# OwlModular.net
KiCad netlist of a schematic drawn in EAGLE
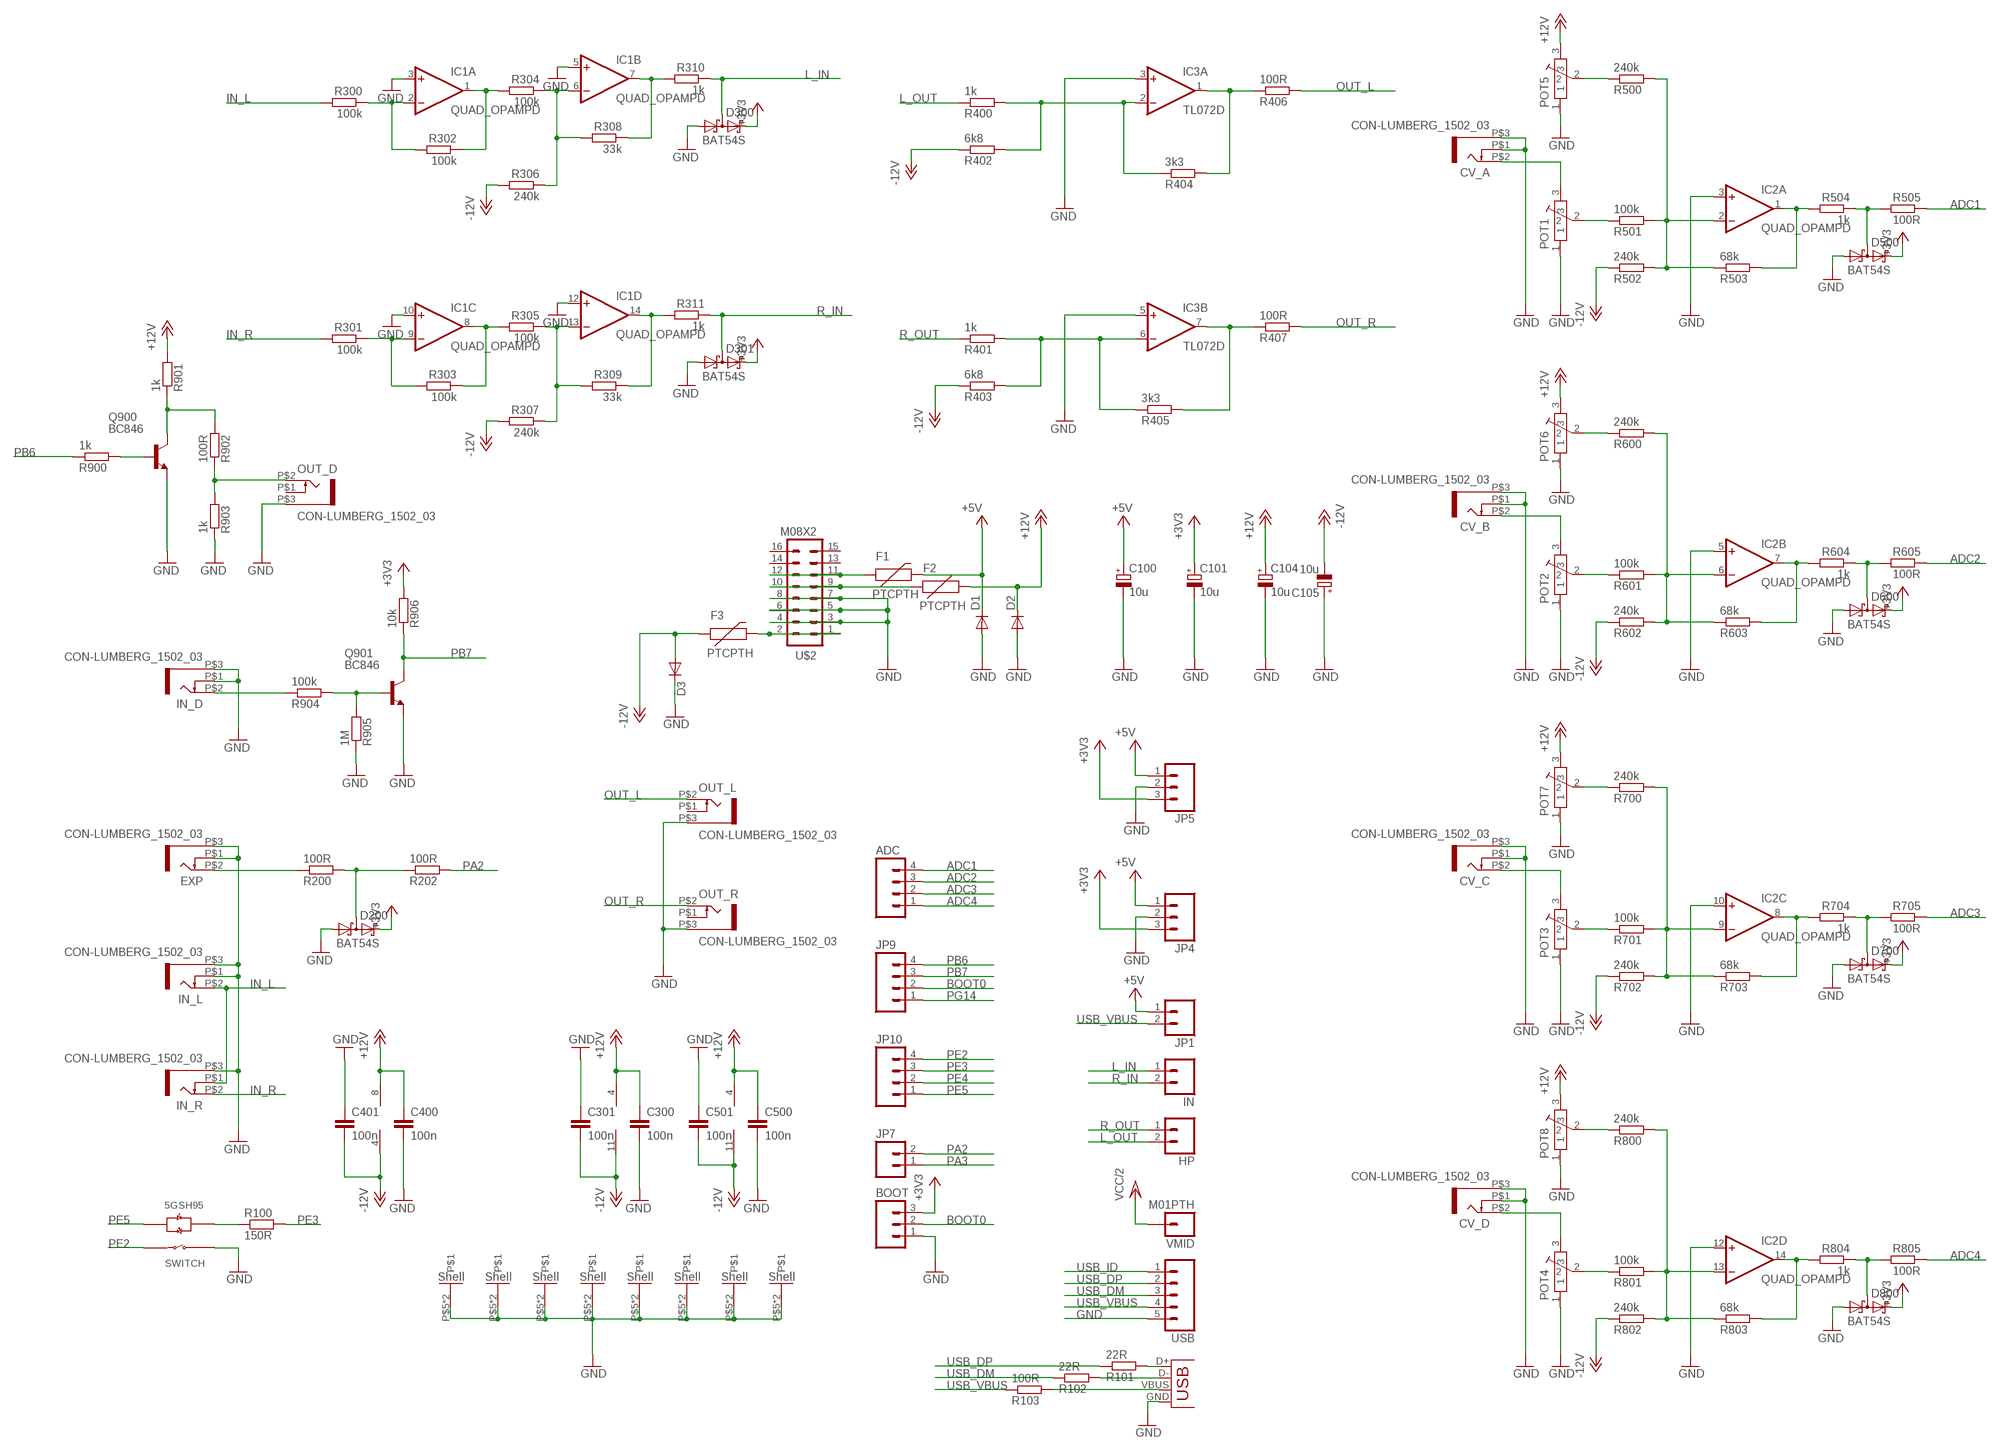
[diagram p0: schematic, sheet 1]

(export (version "E")
  (design (tool "Eeschema 10.0.6"))
  (components
    (comp (ref "ADC")
      (value "M04PTH")
      (footprint "eagle-import:1X04")
      (libsource (lib "eagle-import") (part "M04PTH"))
    )
    (comp (ref "BOOT")
      (value "M03PTH")
      (footprint "eagle-import:1X03")
      (libsource (lib "eagle-import") (part "M03PTH"))
    )
    (comp (ref "C100")
      (value "10u")
      (footprint "eagle-import:PANASONIC_A")
      (libsource (lib "eagle-import") (part "CPOL-EUA"))
    )
    (comp (ref "C101")
      (value "10u")
      (footprint "eagle-import:PANASONIC_A")
      (libsource (lib "eagle-import") (part "CPOL-EUA"))
    )
    (comp (ref "C104")
      (value "10u")
      (footprint "eagle-import:PANASONIC_A")
      (libsource (lib "eagle-import") (part "CPOL-EUA"))
    )
    (comp (ref "C105")
      (value "10u")
      (footprint "eagle-import:PANASONIC_A")
      (libsource (lib "eagle-import") (part "CPOL-EUA"))
    )
    (comp (ref "C300")
      (value "100n")
      (footprint "eagle-import:C0603")
      (libsource (lib "eagle-import") (part "C-EUC0603"))
    )
    (comp (ref "C301")
      (value "100n")
      (footprint "eagle-import:C0603")
      (libsource (lib "eagle-import") (part "C-EUC0603"))
    )
    (comp (ref "C400")
      (value "100n")
      (footprint "eagle-import:C0603")
      (libsource (lib "eagle-import") (part "C-EUC0603"))
    )
    (comp (ref "C401")
      (value "100n")
      (footprint "eagle-import:C0603")
      (libsource (lib "eagle-import") (part "C-EUC0603"))
    )
    (comp (ref "C500")
      (value "100n")
      (footprint "eagle-import:C0603")
      (libsource (lib "eagle-import") (part "C-EUC0603"))
    )
    (comp (ref "C501")
      (value "100n")
      (footprint "eagle-import:C0603")
      (libsource (lib "eagle-import") (part "C-EUC0603"))
    )
    (comp (ref "CV_A")
      (value "CON-LUMBERG_1502_03")
      (footprint "eagle-import:CON-LUMBERG_1502_03")
      (libsource (lib "eagle-import") (part "CON-LUMBERG_1502_03"))
    )
    (comp (ref "CV_B")
      (value "CON-LUMBERG_1502_03")
      (footprint "eagle-import:CON-LUMBERG_1502_03")
      (libsource (lib "eagle-import") (part "CON-LUMBERG_1502_03"))
    )
    (comp (ref "CV_C")
      (value "CON-LUMBERG_1502_03")
      (footprint "eagle-import:CON-LUMBERG_1502_03")
      (libsource (lib "eagle-import") (part "CON-LUMBERG_1502_03"))
    )
    (comp (ref "CV_D")
      (value "CON-LUMBERG_1502_03")
      (footprint "eagle-import:CON-LUMBERG_1502_03")
      (libsource (lib "eagle-import") (part "CON-LUMBERG_1502_03"))
    )
    (comp (ref "D1")
      (value "DIODE1N4001")
      (footprint "eagle-import:DIODE-1N4001")
      (libsource (lib "eagle-import") (part "DIODE1N4001"))
    )
    (comp (ref "D2")
      (value "DIODE1N4001")
      (footprint "eagle-import:DIODE-1N4001")
      (libsource (lib "eagle-import") (part "DIODE1N4001"))
    )
    (comp (ref "D3")
      (value "DIODE1N4001")
      (footprint "eagle-import:DIODE-1N4001")
      (libsource (lib "eagle-import") (part "DIODE1N4001"))
    )
    (comp (ref "D200")
      (value "BAT54S")
      (footprint "eagle-import:SOT23")
      (libsource (lib "eagle-import") (part "BAT54S"))
    )
    (comp (ref "D300")
      (value "BAT54S")
      (footprint "eagle-import:SOT23")
      (libsource (lib "eagle-import") (part "BAT54S"))
    )
    (comp (ref "D301")
      (value "BAT54S")
      (footprint "eagle-import:SOT23")
      (libsource (lib "eagle-import") (part "BAT54S"))
    )
    (comp (ref "D500")
      (value "BAT54S")
      (footprint "eagle-import:SOT23")
      (libsource (lib "eagle-import") (part "BAT54S"))
    )
    (comp (ref "D600")
      (value "BAT54S")
      (footprint "eagle-import:SOT23")
      (libsource (lib "eagle-import") (part "BAT54S"))
    )
    (comp (ref "D700")
      (value "BAT54S")
      (footprint "eagle-import:SOT23")
      (libsource (lib "eagle-import") (part "BAT54S"))
    )
    (comp (ref "D800")
      (value "BAT54S")
      (footprint "eagle-import:SOT23")
      (libsource (lib "eagle-import") (part "BAT54S"))
    )
    (comp (ref "EXP")
      (value "CON-LUMBERG_1502_03")
      (footprint "eagle-import:CON-LUMBERG_1502_03")
      (libsource (lib "eagle-import") (part "CON-LUMBERG_1502_03"))
    )
    (comp (ref "F1")
      (value "PTCPTH")
      (footprint "eagle-import:PTC")
      (libsource (lib "eagle-import") (part "PTCPTH"))
    )
    (comp (ref "F2")
      (value "PTCPTH")
      (footprint "eagle-import:PTC")
      (libsource (lib "eagle-import") (part "PTCPTH"))
    )
    (comp (ref "F3")
      (value "PTCPTH")
      (footprint "eagle-import:PTC")
      (libsource (lib "eagle-import") (part "PTCPTH"))
    )
    (comp (ref "HP")
      (value "M02PTH")
      (footprint "eagle-import:1X02")
      (libsource (lib "eagle-import") (part "M02PTH"))
    )
    (comp (ref "IC1")
      (value "QUAD_OPAMPD")
      (footprint "eagle-import:SO14")
      (libsource (lib "eagle-import") (part "QUAD_OPAMPD"))
    )
    (comp (ref "IC2")
      (value "QUAD_OPAMPD")
      (footprint "eagle-import:SO14")
      (libsource (lib "eagle-import") (part "QUAD_OPAMPD"))
    )
    (comp (ref "IC3")
      (value "TL072D")
      (footprint "eagle-import:SO08")
      (libsource (lib "eagle-import") (part "TL072D"))
    )
    (comp (ref "IN")
      (value "M02PTH")
      (footprint "eagle-import:1X02")
      (libsource (lib "eagle-import") (part "M02PTH"))
    )
    (comp (ref "IN_D")
      (value "CON-LUMBERG_1502_03")
      (footprint "eagle-import:CON-LUMBERG_1502_03")
      (libsource (lib "eagle-import") (part "CON-LUMBERG_1502_03"))
    )
    (comp (ref "IN_L")
      (value "CON-LUMBERG_1502_03")
      (footprint "eagle-import:CON-LUMBERG_1502_03")
      (libsource (lib "eagle-import") (part "CON-LUMBERG_1502_03"))
    )
    (comp (ref "IN_R")
      (value "CON-LUMBERG_1502_03")
      (footprint "eagle-import:CON-LUMBERG_1502_03")
      (libsource (lib "eagle-import") (part "CON-LUMBERG_1502_03"))
    )
    (comp (ref "JP1")
      (value "M02PTH")
      (footprint "eagle-import:1X02")
      (libsource (lib "eagle-import") (part "M02PTH"))
    )
    (comp (ref "JP4")
      (value "M03PTH")
      (footprint "eagle-import:1X03")
      (libsource (lib "eagle-import") (part "M03PTH"))
    )
    (comp (ref "JP5")
      (value "M03PTH")
      (footprint "eagle-import:1X03")
      (libsource (lib "eagle-import") (part "M03PTH"))
    )
    (comp (ref "JP7")
      (value "M02PTH")
      (footprint "eagle-import:1X02")
      (libsource (lib "eagle-import") (part "M02PTH"))
    )
    (comp (ref "JP9")
      (value "M04PTH")
      (footprint "eagle-import:1X04")
      (libsource (lib "eagle-import") (part "M04PTH"))
    )
    (comp (ref "JP10")
      (value "M04PTH")
      (footprint "eagle-import:1X04")
      (libsource (lib "eagle-import") (part "M04PTH"))
    )
    (comp (ref "OUT_D")
      (value "CON-LUMBERG_1502_03")
      (footprint "eagle-import:CON-LUMBERG_1502_03")
      (libsource (lib "eagle-import") (part "CON-LUMBERG_1502_03"))
    )
    (comp (ref "OUT_L")
      (value "CON-LUMBERG_1502_03")
      (footprint "eagle-import:CON-LUMBERG_1502_03")
      (libsource (lib "eagle-import") (part "CON-LUMBERG_1502_03"))
    )
    (comp (ref "OUT_R")
      (value "CON-LUMBERG_1502_03")
      (footprint "eagle-import:CON-LUMBERG_1502_03")
      (libsource (lib "eagle-import") (part "CON-LUMBERG_1502_03"))
    )
    (comp (ref "POT1")
      (value "POT-ALPS-RK09L1140")
      (footprint "eagle-import:POT-ALPS-RK09L1140")
      (libsource (lib "eagle-import") (part "POT-ALPS-RK09L1140"))
    )
    (comp (ref "POT2")
      (value "POT-ALPS-RK09L1140")
      (footprint "eagle-import:POT-ALPS-RK09L1140")
      (libsource (lib "eagle-import") (part "POT-ALPS-RK09L1140"))
    )
    (comp (ref "POT3")
      (value "POT-ALPS-RK09L1140")
      (footprint "eagle-import:POT-ALPS-RK09L1140")
      (libsource (lib "eagle-import") (part "POT-ALPS-RK09L1140"))
    )
    (comp (ref "POT4")
      (value "POT-ALPS-RK09L1140")
      (footprint "eagle-import:POT-ALPS-RK09L1140")
      (libsource (lib "eagle-import") (part "POT-ALPS-RK09L1140"))
    )
    (comp (ref "POT5")
      (value "POT-ALPS-RK09L1140")
      (footprint "eagle-import:POT-ALPS-RK09L1140")
      (libsource (lib "eagle-import") (part "POT-ALPS-RK09L1140"))
    )
    (comp (ref "POT6")
      (value "POT-ALPS-RK09L1140")
      (footprint "eagle-import:POT-ALPS-RK09L1140")
      (libsource (lib "eagle-import") (part "POT-ALPS-RK09L1140"))
    )
    (comp (ref "POT7")
      (value "POT-ALPS-RK09L1140")
      (footprint "eagle-import:POT-ALPS-RK09L1140")
      (libsource (lib "eagle-import") (part "POT-ALPS-RK09L1140"))
    )
    (comp (ref "POT8")
      (value "POT-ALPS-RK09L1140")
      (footprint "eagle-import:POT-ALPS-RK09L1140")
      (libsource (lib "eagle-import") (part "POT-ALPS-RK09L1140"))
    )
    (comp (ref "Q900")
      (value "BC846")
      (footprint "eagle-import:SOT23")
      (libsource (lib "eagle-import") (part "BC846"))
    )
    (comp (ref "Q901")
      (value "BC846")
      (footprint "eagle-import:SOT23")
      (libsource (lib "eagle-import") (part "BC846"))
    )
    (comp (ref "R100")
      (value "150R")
      (footprint "eagle-import:0603")
      (libsource (lib "eagle-import") (part "R-EU_0603"))
    )
    (comp (ref "R101")
      (value "22R")
      (footprint "eagle-import:0603")
      (libsource (lib "eagle-import") (part "R-EU_0603"))
    )
    (comp (ref "R102")
      (value "22R")
      (footprint "eagle-import:0603")
      (libsource (lib "eagle-import") (part "R-EU_0603"))
    )
    (comp (ref "R103")
      (value "100R")
      (footprint "eagle-import:0603")
      (libsource (lib "eagle-import") (part "R-EU_0603"))
    )
    (comp (ref "R200")
      (value "100R")
      (footprint "eagle-import:0603")
      (libsource (lib "eagle-import") (part "R-EU_0603"))
    )
    (comp (ref "R202")
      (value "100R")
      (footprint "eagle-import:0603")
      (libsource (lib "eagle-import") (part "R-EU_0603"))
    )
    (comp (ref "R300")
      (value "100k")
      (footprint "eagle-import:0603")
      (libsource (lib "eagle-import") (part "R-EU_0603"))
    )
    (comp (ref "R301")
      (value "100k")
      (footprint "eagle-import:0603")
      (libsource (lib "eagle-import") (part "R-EU_0603"))
    )
    (comp (ref "R302")
      (value "100k")
      (footprint "eagle-import:0603")
      (libsource (lib "eagle-import") (part "R-EU_0603"))
    )
    (comp (ref "R303")
      (value "100k")
      (footprint "eagle-import:0603")
      (libsource (lib "eagle-import") (part "R-EU_0603"))
    )
    (comp (ref "R304")
      (value "100k")
      (footprint "eagle-import:0603")
      (libsource (lib "eagle-import") (part "R-EU_0603"))
    )
    (comp (ref "R305")
      (value "100k")
      (footprint "eagle-import:0603")
      (libsource (lib "eagle-import") (part "R-EU_0603"))
    )
    (comp (ref "R306")
      (value "240k")
      (footprint "eagle-import:0603")
      (libsource (lib "eagle-import") (part "R-EU_0603"))
    )
    (comp (ref "R307")
      (value "240k")
      (footprint "eagle-import:0603")
      (libsource (lib "eagle-import") (part "R-EU_0603"))
    )
    (comp (ref "R308")
      (value "33k")
      (footprint "eagle-import:0603")
      (libsource (lib "eagle-import") (part "R-EU_0603"))
    )
    (comp (ref "R309")
      (value "33k")
      (footprint "eagle-import:0603")
      (libsource (lib "eagle-import") (part "R-EU_0603"))
    )
    (comp (ref "R310")
      (value "1k")
      (footprint "eagle-import:0603")
      (libsource (lib "eagle-import") (part "R-EU_0603"))
    )
    (comp (ref "R311")
      (value "1k")
      (footprint "eagle-import:0603")
      (libsource (lib "eagle-import") (part "R-EU_0603"))
    )
    (comp (ref "R400")
      (value "1k")
      (footprint "eagle-import:0603")
      (libsource (lib "eagle-import") (part "R-EU_0603"))
    )
    (comp (ref "R401")
      (value "1k")
      (footprint "eagle-import:0603")
      (libsource (lib "eagle-import") (part "R-EU_0603"))
    )
    (comp (ref "R402")
      (value "6k8")
      (footprint "eagle-import:0603")
      (libsource (lib "eagle-import") (part "R-EU_0603"))
    )
    (comp (ref "R403")
      (value "6k8")
      (footprint "eagle-import:0603")
      (libsource (lib "eagle-import") (part "R-EU_0603"))
    )
    (comp (ref "R404")
      (value "3k3")
      (footprint "eagle-import:0603")
      (libsource (lib "eagle-import") (part "R-EU_0603"))
    )
    (comp (ref "R405")
      (value "3k3")
      (footprint "eagle-import:0603")
      (libsource (lib "eagle-import") (part "R-EU_0603"))
    )
    (comp (ref "R406")
      (value "100R")
      (footprint "eagle-import:0603")
      (libsource (lib "eagle-import") (part "R-EU_0603"))
    )
    (comp (ref "R407")
      (value "100R")
      (footprint "eagle-import:0603")
      (libsource (lib "eagle-import") (part "R-EU_0603"))
    )
    (comp (ref "R500")
      (value "240k")
      (footprint "eagle-import:0603")
      (libsource (lib "eagle-import") (part "R-EU_0603"))
    )
    (comp (ref "R501")
      (value "100k")
      (footprint "eagle-import:0603")
      (libsource (lib "eagle-import") (part "R-EU_0603"))
    )
    (comp (ref "R502")
      (value "240k")
      (footprint "eagle-import:0603")
      (libsource (lib "eagle-import") (part "R-EU_0603"))
    )
    (comp (ref "R503")
      (value "68k")
      (footprint "eagle-import:0603")
      (libsource (lib "eagle-import") (part "R-EU_0603"))
    )
    (comp (ref "R504")
      (value "1k")
      (footprint "eagle-import:0603")
      (libsource (lib "eagle-import") (part "R-EU_0603"))
    )
    (comp (ref "R505")
      (value "100R")
      (footprint "eagle-import:0603")
      (libsource (lib "eagle-import") (part "R-EU_0603"))
    )
    (comp (ref "R600")
      (value "240k")
      (footprint "eagle-import:0603")
      (libsource (lib "eagle-import") (part "R-EU_0603"))
    )
    (comp (ref "R601")
      (value "100k")
      (footprint "eagle-import:0603")
      (libsource (lib "eagle-import") (part "R-EU_0603"))
    )
    (comp (ref "R602")
      (value "240k")
      (footprint "eagle-import:0603")
      (libsource (lib "eagle-import") (part "R-EU_0603"))
    )
    (comp (ref "R603")
      (value "68k")
      (footprint "eagle-import:0603")
      (libsource (lib "eagle-import") (part "R-EU_0603"))
    )
    (comp (ref "R604")
      (value "1k")
      (footprint "eagle-import:0603")
      (libsource (lib "eagle-import") (part "R-EU_0603"))
    )
    (comp (ref "R605")
      (value "100R")
      (footprint "eagle-import:0603")
      (libsource (lib "eagle-import") (part "R-EU_0603"))
    )
    (comp (ref "R700")
      (value "240k")
      (footprint "eagle-import:0603")
      (libsource (lib "eagle-import") (part "R-EU_0603"))
    )
    (comp (ref "R701")
      (value "100k")
      (footprint "eagle-import:0603")
      (libsource (lib "eagle-import") (part "R-EU_0603"))
    )
    (comp (ref "R702")
      (value "240k")
      (footprint "eagle-import:0603")
      (libsource (lib "eagle-import") (part "R-EU_0603"))
    )
    (comp (ref "R703")
      (value "68k")
      (footprint "eagle-import:0603")
      (libsource (lib "eagle-import") (part "R-EU_0603"))
    )
    (comp (ref "R704")
      (value "1k")
      (footprint "eagle-import:0603")
      (libsource (lib "eagle-import") (part "R-EU_0603"))
    )
    (comp (ref "R705")
      (value "100R")
      (footprint "eagle-import:0603")
      (libsource (lib "eagle-import") (part "R-EU_0603"))
    )
    (comp (ref "R800")
      (value "240k")
      (footprint "eagle-import:0603")
      (libsource (lib "eagle-import") (part "R-EU_0603"))
    )
    (comp (ref "R801")
      (value "100k")
      (footprint "eagle-import:0603")
      (libsource (lib "eagle-import") (part "R-EU_0603"))
    )
    (comp (ref "R802")
      (value "240k")
      (footprint "eagle-import:0603")
      (libsource (lib "eagle-import") (part "R-EU_0603"))
    )
    (comp (ref "R803")
      (value "68k")
      (footprint "eagle-import:0603")
      (libsource (lib "eagle-import") (part "R-EU_0603"))
    )
    (comp (ref "R804")
      (value "1k")
      (footprint "eagle-import:0603")
      (libsource (lib "eagle-import") (part "R-EU_0603"))
    )
    (comp (ref "R805")
      (value "100R")
      (footprint "eagle-import:0603")
      (libsource (lib "eagle-import") (part "R-EU_0603"))
    )
    (comp (ref "R900")
      (value "1k")
      (footprint "eagle-import:0603")
      (libsource (lib "eagle-import") (part "R-EU_0603"))
    )
    (comp (ref "R901")
      (value "1k")
      (footprint "eagle-import:0603")
      (libsource (lib "eagle-import") (part "R-EU_0603"))
    )
    (comp (ref "R902")
      (value "100R")
      (footprint "eagle-import:0603")
      (libsource (lib "eagle-import") (part "R-EU_0603"))
    )
    (comp (ref "R903")
      (value "1k")
      (footprint "eagle-import:0603")
      (libsource (lib "eagle-import") (part "R-EU_0603"))
    )
    (comp (ref "R904")
      (value "100k")
      (footprint "eagle-import:0603")
      (libsource (lib "eagle-import") (part "R-EU_0603"))
    )
    (comp (ref "R905")
      (value "1M")
      (footprint "eagle-import:0603")
      (libsource (lib "eagle-import") (part "R-EU_0603"))
    )
    (comp (ref "R906")
      (value "10k")
      (footprint "eagle-import:0603")
      (libsource (lib "eagle-import") (part "R-EU_0603"))
    )
    (comp (ref "U$1")
      (value "5GTH9")
      (footprint "eagle-import:5GTH9")
      (libsource (lib "eagle-import") (part "5GTH9"))
    )
    (comp (ref "U$2")
      (value "M08X2")
      (footprint "eagle-import:2X8")
      (libsource (lib "eagle-import") (part "M08X2"))
    )
    (comp (ref "USB")
      (value "M05PTH")
      (footprint "eagle-import:1X05")
      (libsource (lib "eagle-import") (part "M05PTH"))
    )
    (comp (ref "VMID")
      (value "M01PTH")
      (footprint "eagle-import:1X01")
      (libsource (lib "eagle-import") (part "M01PTH"))
    )
    (comp (ref "X1")
      (value "USBPTH-VERTICAL")
      (footprint "eagle-import:USB-B-PTH-VERTICAL")
      (libsource (lib "eagle-import") (part "USBPTH-VERTICAL"))
    )
  )
  (nets
    (net (code "1") (name "+3V3") (class "Default")
      (node (ref "BOOT") (pin "3") (pinfunction "3_3") (pintype "passive"))
      (node (ref "C101") (pin "+") (pinfunction "+_+") (pintype "passive"))
      (node (ref "D200") (pin "2") (pinfunction "C2_2") (pintype "passive"))
      (node (ref "D300") (pin "2") (pinfunction "C2_2") (pintype "passive"))
      (node (ref "D301") (pin "2") (pinfunction "C2_2") (pintype "passive"))
      (node (ref "D500") (pin "2") (pinfunction "C2_2") (pintype "passive"))
      (node (ref "D600") (pin "2") (pinfunction "C2_2") (pintype "passive"))
      (node (ref "D700") (pin "2") (pinfunction "C2_2") (pintype "passive"))
      (node (ref "D800") (pin "2") (pinfunction "C2_2") (pintype "passive"))
      (node (ref "JP4") (pin "3") (pinfunction "3_3") (pintype "passive"))
      (node (ref "JP5") (pin "3") (pinfunction "3_3") (pintype "passive"))
      (node (ref "R906") (pin "2") (pinfunction "2_2") (pintype "passive"))
    )
    (net (code "2") (name "+5V") (class "Default")
      (node (ref "C100") (pin "+") (pinfunction "+_+") (pintype "passive"))
      (node (ref "D1") (pin "C") (pinfunction "C_C") (pintype "passive"))
      (node (ref "F1") (pin "P$2") (pinfunction "2_P$2") (pintype "bidirectional"))
      (node (ref "JP1") (pin "1") (pinfunction "1_1") (pintype "passive"))
      (node (ref "JP4") (pin "1") (pinfunction "1_1") (pintype "passive"))
      (node (ref "JP5") (pin "1") (pinfunction "1_1") (pintype "passive"))
    )
    (net (code "3") (name "+12V") (class "Default")
      (node (ref "C104") (pin "+") (pinfunction "+_+") (pintype "passive"))
      (node (ref "C300") (pin "1") (pinfunction "1_1") (pintype "passive"))
      (node (ref "C400") (pin "1") (pinfunction "1_1") (pintype "passive"))
      (node (ref "C500") (pin "1") (pinfunction "1_1") (pintype "passive"))
      (node (ref "D2") (pin "C") (pinfunction "C_C") (pintype "passive"))
      (node (ref "F2") (pin "P$2") (pinfunction "2_P$2") (pintype "bidirectional"))
      (node (ref "IC1") (pin "4") (pinfunction "V+_4") (pintype "power_in"))
      (node (ref "IC2") (pin "4") (pinfunction "V+_4") (pintype "power_in"))
      (node (ref "IC3") (pin "8") (pinfunction "V+_8") (pintype "power_in"))
      (node (ref "POT5") (pin "3") (pinfunction "3_3") (pintype "bidirectional"))
      (node (ref "POT6") (pin "3") (pinfunction "3_3") (pintype "bidirectional"))
      (node (ref "POT7") (pin "3") (pinfunction "3_3") (pintype "bidirectional"))
      (node (ref "POT8") (pin "3") (pinfunction "3_3") (pintype "bidirectional"))
      (node (ref "R901") (pin "2") (pinfunction "2_2") (pintype "passive"))
    )
    (net (code "4") (name "-12V") (class "Default")
      (node (ref "C105") (pin "-") (pinfunction "-_-") (pintype "passive"))
      (node (ref "C301") (pin "2") (pinfunction "2_2") (pintype "passive"))
      (node (ref "C401") (pin "2") (pinfunction "2_2") (pintype "passive"))
      (node (ref "C501") (pin "2") (pinfunction "2_2") (pintype "passive"))
      (node (ref "D3") (pin "A") (pinfunction "A_A") (pintype "passive"))
      (node (ref "F3") (pin "P$1") (pinfunction "1_P$1") (pintype "bidirectional"))
      (node (ref "IC1") (pin "11") (pinfunction "V-_11") (pintype "power_in"))
      (node (ref "IC2") (pin "11") (pinfunction "V-_11") (pintype "power_in"))
      (node (ref "IC3") (pin "4") (pinfunction "V-_4") (pintype "power_in"))
      (node (ref "R306") (pin "2") (pinfunction "2_2") (pintype "passive"))
      (node (ref "R307") (pin "2") (pinfunction "2_2") (pintype "passive"))
      (node (ref "R402") (pin "1") (pinfunction "1_1") (pintype "passive"))
      (node (ref "R403") (pin "1") (pinfunction "1_1") (pintype "passive"))
      (node (ref "R502") (pin "1") (pinfunction "1_1") (pintype "passive"))
      (node (ref "R602") (pin "1") (pinfunction "1_1") (pintype "passive"))
      (node (ref "R702") (pin "1") (pinfunction "1_1") (pintype "passive"))
      (node (ref "R802") (pin "1") (pinfunction "1_1") (pintype "passive"))
    )
    (net (code "5") (name "/ADC1") (class "Default")
      (node (ref "ADC") (pin "4") (pinfunction "4_4") (pintype "passive"))
      (node (ref "R505") (pin "1") (pinfunction "1_1") (pintype "passive"))
    )
    (net (code "6") (name "/ADC2") (class "Default")
      (node (ref "ADC") (pin "3") (pinfunction "3_3") (pintype "passive"))
      (node (ref "R605") (pin "1") (pinfunction "1_1") (pintype "passive"))
    )
    (net (code "7") (name "/ADC3") (class "Default")
      (node (ref "ADC") (pin "2") (pinfunction "2_2") (pintype "passive"))
      (node (ref "R705") (pin "1") (pinfunction "1_1") (pintype "passive"))
    )
    (net (code "8") (name "/ADC4") (class "Default")
      (node (ref "ADC") (pin "1") (pinfunction "1_1") (pintype "passive"))
      (node (ref "R805") (pin "1") (pinfunction "1_1") (pintype "passive"))
    )
    (net (code "9") (name "/BOOT0") (class "Default")
      (node (ref "BOOT") (pin "2") (pinfunction "2_2") (pintype "passive"))
      (node (ref "JP9") (pin "2") (pinfunction "2_2") (pintype "passive"))
    )
    (net (code "10") (name "/IN_L") (class "Default")
      (node (ref "IN_L") (pin "P$2") (pinfunction "3_P$2") (pintype "passive"))
      (node (ref "IN_R") (pin "P$1") (pinfunction "4_P$1") (pintype "passive"))
      (node (ref "R300") (pin "2") (pinfunction "2_2") (pintype "passive"))
    )
    (net (code "11") (name "/IN_R") (class "Default")
      (node (ref "IN_R") (pin "P$2") (pinfunction "3_P$2") (pintype "passive"))
      (node (ref "R301") (pin "2") (pinfunction "2_2") (pintype "passive"))
    )
    (net (code "12") (name "/L_IN") (class "Default")
      (node (ref "D300") (pin "3") (pinfunction "C1A2_3") (pintype "passive"))
      (node (ref "IN") (pin "1") (pinfunction "1_1") (pintype "passive"))
      (node (ref "R310") (pin "1") (pinfunction "1_1") (pintype "passive"))
    )
    (net (code "13") (name "/L_OUT") (class "Default")
      (node (ref "HP") (pin "2") (pinfunction "2_2") (pintype "passive"))
      (node (ref "R400") (pin "1") (pinfunction "1_1") (pintype "passive"))
    )
    (net (code "14") (name "/OUT_L") (class "Default")
      (node (ref "OUT_L") (pin "P$2") (pinfunction "3_P$2") (pintype "passive"))
      (node (ref "R406") (pin "2") (pinfunction "2_2") (pintype "passive"))
    )
    (net (code "15") (name "/OUT_R") (class "Default")
      (node (ref "OUT_R") (pin "P$2") (pinfunction "3_P$2") (pintype "passive"))
      (node (ref "R407") (pin "2") (pinfunction "2_2") (pintype "passive"))
    )
    (net (code "16") (name "/PA2") (class "Default")
      (node (ref "JP7") (pin "2") (pinfunction "2_2") (pintype "passive"))
      (node (ref "R202") (pin "2") (pinfunction "2_2") (pintype "passive"))
    )
    (net (code "17") (name "/PA3") (class "Default")
      (node (ref "JP7") (pin "1") (pinfunction "1_1") (pintype "passive"))
    )
    (net (code "18") (name "/PB6") (class "Default")
      (node (ref "JP9") (pin "4") (pinfunction "4_4") (pintype "passive"))
      (node (ref "R900") (pin "1") (pinfunction "1_1") (pintype "passive"))
    )
    (net (code "19") (name "/PB7") (class "Default")
      (node (ref "JP9") (pin "3") (pinfunction "3_3") (pintype "passive"))
      (node (ref "Q901") (pin "3") (pinfunction "C_3") (pintype "passive"))
      (node (ref "R906") (pin "1") (pinfunction "1_1") (pintype "passive"))
    )
    (net (code "20") (name "/PE2") (class "Default")
      (node (ref "JP10") (pin "4") (pinfunction "4_4") (pintype "passive"))
      (node (ref "U$1") (pin "4") (pinfunction "SWITCH_A_4") (pintype "power_in"))
    )
    (net (code "21") (name "/PE3") (class "Default")
      (node (ref "JP10") (pin "3") (pinfunction "3_3") (pintype "passive"))
      (node (ref "R100") (pin "2") (pinfunction "2_2") (pintype "passive"))
    )
    (net (code "22") (name "/PE4") (class "Default")
      (node (ref "JP10") (pin "2") (pinfunction "2_2") (pintype "passive"))
    )
    (net (code "23") (name "/PE5") (class "Default")
      (node (ref "JP10") (pin "1") (pinfunction "1_1") (pintype "passive"))
      (node (ref "U$1") (pin "-2") (pinfunction "LED_G+_-2") (pintype "input"))
    )
    (net (code "24") (name "/PG14") (class "Default")
      (node (ref "JP9") (pin "1") (pinfunction "1_1") (pintype "passive"))
    )
    (net (code "25") (name "/R_IN") (class "Default")
      (node (ref "D301") (pin "3") (pinfunction "C1A2_3") (pintype "passive"))
      (node (ref "IN") (pin "2") (pinfunction "2_2") (pintype "passive"))
      (node (ref "R311") (pin "1") (pinfunction "1_1") (pintype "passive"))
    )
    (net (code "26") (name "/R_OUT") (class "Default")
      (node (ref "HP") (pin "1") (pinfunction "1_1") (pintype "passive"))
      (node (ref "R401") (pin "1") (pinfunction "1_1") (pintype "passive"))
    )
    (net (code "27") (name "/USB_DM") (class "Default")
      (node (ref "R102") (pin "1") (pinfunction "1_1") (pintype "passive"))
      (node (ref "USB") (pin "3") (pinfunction "3_3") (pintype "passive"))
    )
    (net (code "28") (name "/USB_DP") (class "Default")
      (node (ref "R101") (pin "1") (pinfunction "1_1") (pintype "passive"))
      (node (ref "USB") (pin "2") (pinfunction "2_2") (pintype "passive"))
    )
    (net (code "29") (name "/USB_ID") (class "Default")
      (node (ref "USB") (pin "1") (pinfunction "1_1") (pintype "passive"))
    )
    (net (code "30") (name "/USB_VBUS") (class "Default")
      (node (ref "JP1") (pin "2") (pinfunction "2_2") (pintype "passive"))
      (node (ref "R103") (pin "1") (pinfunction "1_1") (pintype "passive"))
      (node (ref "USB") (pin "4") (pinfunction "4_4") (pintype "passive"))
    )
    (net (code "31") (name "GND") (class "Default")
      (node (ref "BOOT") (pin "1") (pinfunction "1_1") (pintype "passive"))
      (node (ref "C100") (pin "-") (pinfunction "-_-") (pintype "passive"))
      (node (ref "C101") (pin "-") (pinfunction "-_-") (pintype "passive"))
      (node (ref "C104") (pin "-") (pinfunction "-_-") (pintype "passive"))
      (node (ref "C105") (pin "+") (pinfunction "+_+") (pintype "passive"))
      (node (ref "C300") (pin "2") (pinfunction "2_2") (pintype "passive"))
      (node (ref "C301") (pin "1") (pinfunction "1_1") (pintype "passive"))
      (node (ref "C400") (pin "2") (pinfunction "2_2") (pintype "passive"))
      (node (ref "C401") (pin "1") (pinfunction "1_1") (pintype "passive"))
      (node (ref "C500") (pin "2") (pinfunction "2_2") (pintype "passive"))
      (node (ref "C501") (pin "1") (pinfunction "1_1") (pintype "passive"))
      (node (ref "CV_A") (pin "P$1") (pinfunction "4_P$1") (pintype "passive"))
      (node (ref "CV_A") (pin "P$3") (pinfunction "5_P$3") (pintype "passive"))
      (node (ref "CV_B") (pin "P$1") (pinfunction "4_P$1") (pintype "passive"))
      (node (ref "CV_B") (pin "P$3") (pinfunction "5_P$3") (pintype "passive"))
      (node (ref "CV_C") (pin "P$1") (pinfunction "4_P$1") (pintype "passive"))
      (node (ref "CV_C") (pin "P$3") (pinfunction "5_P$3") (pintype "passive"))
      (node (ref "CV_D") (pin "P$1") (pinfunction "4_P$1") (pintype "passive"))
      (node (ref "CV_D") (pin "P$3") (pinfunction "5_P$3") (pintype "passive"))
      (node (ref "D1") (pin "A") (pinfunction "A_A") (pintype "passive"))
      (node (ref "D2") (pin "A") (pinfunction "A_A") (pintype "passive"))
      (node (ref "D200") (pin "1") (pinfunction "A1_1") (pintype "passive"))
      (node (ref "D3") (pin "C") (pinfunction "C_C") (pintype "passive"))
      (node (ref "D300") (pin "1") (pinfunction "A1_1") (pintype "passive"))
      (node (ref "D301") (pin "1") (pinfunction "A1_1") (pintype "passive"))
      (node (ref "D500") (pin "1") (pinfunction "A1_1") (pintype "passive"))
      (node (ref "D600") (pin "1") (pinfunction "A1_1") (pintype "passive"))
      (node (ref "D700") (pin "1") (pinfunction "A1_1") (pintype "passive"))
      (node (ref "D800") (pin "1") (pinfunction "A1_1") (pintype "passive"))
      (node (ref "EXP") (pin "P$1") (pinfunction "4_P$1") (pintype "passive"))
      (node (ref "EXP") (pin "P$3") (pinfunction "5_P$3") (pintype "passive"))
      (node (ref "IC1") (pin "10") (pinfunction "+IN_10") (pintype "input"))
      (node (ref "IC1") (pin "12") (pinfunction "+IN_12") (pintype "input"))
      (node (ref "IC1") (pin "3") (pinfunction "+IN_3") (pintype "input"))
      (node (ref "IC1") (pin "5") (pinfunction "+IN_5") (pintype "input"))
      (node (ref "IC2") (pin "10") (pinfunction "+IN_10") (pintype "input"))
      (node (ref "IC2") (pin "12") (pinfunction "+IN_12") (pintype "input"))
      (node (ref "IC2") (pin "3") (pinfunction "+IN_3") (pintype "input"))
      (node (ref "IC2") (pin "5") (pinfunction "+IN_5") (pintype "input"))
      (node (ref "IC3") (pin "3") (pinfunction "+IN_3") (pintype "input"))
      (node (ref "IC3") (pin "5") (pinfunction "+IN_5") (pintype "input"))
      (node (ref "IN_D") (pin "P$1") (pinfunction "4_P$1") (pintype "passive"))
      (node (ref "IN_D") (pin "P$3") (pinfunction "5_P$3") (pintype "passive"))
      (node (ref "IN_L") (pin "P$1") (pinfunction "4_P$1") (pintype "passive"))
      (node (ref "IN_L") (pin "P$3") (pinfunction "5_P$3") (pintype "passive"))
      (node (ref "IN_R") (pin "P$3") (pinfunction "5_P$3") (pintype "passive"))
      (node (ref "JP4") (pin "2") (pinfunction "2_2") (pintype "passive"))
      (node (ref "JP5") (pin "2") (pinfunction "2_2") (pintype "passive"))
      (node (ref "OUT_D") (pin "P$3") (pinfunction "5_P$3") (pintype "passive"))
      (node (ref "OUT_L") (pin "P$3") (pinfunction "5_P$3") (pintype "passive"))
      (node (ref "OUT_R") (pin "P$3") (pinfunction "5_P$3") (pintype "passive"))
      (node (ref "POT1") (pin "1") (pinfunction "1_1") (pintype "bidirectional"))
      (node (ref "POT1") (pin "P$5") (pinfunction "P$1_P$5") (pintype "bidirectional"))
      (node (ref "POT1") (pin "P$6") (pinfunction "P$1_P$6") (pintype "bidirectional"))
      (node (ref "POT2") (pin "1") (pinfunction "1_1") (pintype "bidirectional"))
      (node (ref "POT2") (pin "P$5") (pinfunction "P$1_P$5") (pintype "bidirectional"))
      (node (ref "POT2") (pin "P$6") (pinfunction "P$1_P$6") (pintype "bidirectional"))
      (node (ref "POT3") (pin "1") (pinfunction "1_1") (pintype "bidirectional"))
      (node (ref "POT3") (pin "P$5") (pinfunction "P$1_P$5") (pintype "bidirectional"))
      (node (ref "POT3") (pin "P$6") (pinfunction "P$1_P$6") (pintype "bidirectional"))
      (node (ref "POT4") (pin "1") (pinfunction "1_1") (pintype "bidirectional"))
      (node (ref "POT4") (pin "P$5") (pinfunction "P$1_P$5") (pintype "bidirectional"))
      (node (ref "POT4") (pin "P$6") (pinfunction "P$1_P$6") (pintype "bidirectional"))
      (node (ref "POT5") (pin "1") (pinfunction "1_1") (pintype "bidirectional"))
      (node (ref "POT5") (pin "P$5") (pinfunction "P$1_P$5") (pintype "bidirectional"))
      (node (ref "POT5") (pin "P$6") (pinfunction "P$1_P$6") (pintype "bidirectional"))
      (node (ref "POT6") (pin "1") (pinfunction "1_1") (pintype "bidirectional"))
      (node (ref "POT6") (pin "P$5") (pinfunction "P$1_P$5") (pintype "bidirectional"))
      (node (ref "POT6") (pin "P$6") (pinfunction "P$1_P$6") (pintype "bidirectional"))
      (node (ref "POT7") (pin "1") (pinfunction "1_1") (pintype "bidirectional"))
      (node (ref "POT7") (pin "P$5") (pinfunction "P$1_P$5") (pintype "bidirectional"))
      (node (ref "POT7") (pin "P$6") (pinfunction "P$1_P$6") (pintype "bidirectional"))
      (node (ref "POT8") (pin "1") (pinfunction "1_1") (pintype "bidirectional"))
      (node (ref "POT8") (pin "P$5") (pinfunction "P$1_P$5") (pintype "bidirectional"))
      (node (ref "POT8") (pin "P$6") (pinfunction "P$1_P$6") (pintype "bidirectional"))
      (node (ref "Q900") (pin "2") (pinfunction "E_2") (pintype "passive"))
      (node (ref "Q901") (pin "2") (pinfunction "E_2") (pintype "passive"))
      (node (ref "R903") (pin "1") (pinfunction "1_1") (pintype "passive"))
      (node (ref "R905") (pin "1") (pinfunction "1_1") (pintype "passive"))
      (node (ref "U$1") (pin "1") (pinfunction "SWITCH_B_1") (pintype "power_in"))
      (node (ref "U$2") (pin "3") (pinfunction "3_3") (pintype "passive"))
      (node (ref "U$2") (pin "4") (pinfunction "4_4") (pintype "passive"))
      (node (ref "U$2") (pin "5") (pinfunction "5_5") (pintype "passive"))
      (node (ref "U$2") (pin "6") (pinfunction "6_6") (pintype "passive"))
      (node (ref "U$2") (pin "7") (pinfunction "7_7") (pintype "passive"))
      (node (ref "U$2") (pin "8") (pinfunction "8_8") (pintype "passive"))
      (node (ref "USB") (pin "5") (pinfunction "5_5") (pintype "passive"))
      (node (ref "X1") (pin "GND") (pinfunction "GND_GND") (pintype "bidirectional"))
    )
    (net (code "32") (name "Net-(CV_A-3)") (class "Default")
      (node (ref "CV_A") (pin "P$2") (pinfunction "3_P$2") (pintype "passive"))
      (node (ref "POT1") (pin "3") (pinfunction "3_3") (pintype "bidirectional"))
    )
    (net (code "33") (name "Net-(CV_B-3)") (class "Default")
      (node (ref "CV_B") (pin "P$2") (pinfunction "3_P$2") (pintype "passive"))
      (node (ref "POT2") (pin "3") (pinfunction "3_3") (pintype "bidirectional"))
    )
    (net (code "34") (name "Net-(CV_C-3)") (class "Default")
      (node (ref "CV_C") (pin "P$2") (pinfunction "3_P$2") (pintype "passive"))
      (node (ref "POT3") (pin "3") (pinfunction "3_3") (pintype "bidirectional"))
    )
    (net (code "35") (name "Net-(CV_D-3)") (class "Default")
      (node (ref "CV_D") (pin "P$2") (pinfunction "3_P$2") (pintype "passive"))
      (node (ref "POT4") (pin "3") (pinfunction "3_3") (pintype "bidirectional"))
    )
    (net (code "36") (name "Net-(D200-C1A2)") (class "Default")
      (node (ref "D200") (pin "3") (pinfunction "C1A2_3") (pintype "passive"))
      (node (ref "R200") (pin "2") (pinfunction "2_2") (pintype "passive"))
      (node (ref "R202") (pin "1") (pinfunction "1_1") (pintype "passive"))
    )
    (net (code "37") (name "Net-(D500-C1A2)") (class "Default")
      (node (ref "D500") (pin "3") (pinfunction "C1A2_3") (pintype "passive"))
      (node (ref "R504") (pin "1") (pinfunction "1_1") (pintype "passive"))
      (node (ref "R505") (pin "2") (pinfunction "2_2") (pintype "passive"))
    )
    (net (code "38") (name "Net-(D600-C1A2)") (class "Default")
      (node (ref "D600") (pin "3") (pinfunction "C1A2_3") (pintype "passive"))
      (node (ref "R604") (pin "1") (pinfunction "1_1") (pintype "passive"))
      (node (ref "R605") (pin "2") (pinfunction "2_2") (pintype "passive"))
    )
    (net (code "39") (name "Net-(D700-C1A2)") (class "Default")
      (node (ref "D700") (pin "3") (pinfunction "C1A2_3") (pintype "passive"))
      (node (ref "R704") (pin "1") (pinfunction "1_1") (pintype "passive"))
      (node (ref "R705") (pin "2") (pinfunction "2_2") (pintype "passive"))
    )
    (net (code "40") (name "Net-(D800-C1A2)") (class "Default")
      (node (ref "D800") (pin "3") (pinfunction "C1A2_3") (pintype "passive"))
      (node (ref "R804") (pin "1") (pinfunction "1_1") (pintype "passive"))
      (node (ref "R805") (pin "2") (pinfunction "2_2") (pintype "passive"))
    )
    (net (code "41") (name "Net-(EXP-3)") (class "Default")
      (node (ref "EXP") (pin "P$2") (pinfunction "3_P$2") (pintype "passive"))
      (node (ref "R200") (pin "1") (pinfunction "1_1") (pintype "passive"))
    )
    (net (code "42") (name "Net-(F1-1)") (class "Default")
      (node (ref "F1") (pin "P$1") (pinfunction "1_P$1") (pintype "bidirectional"))
      (node (ref "U$2") (pin "11") (pinfunction "11_11") (pintype "passive"))
      (node (ref "U$2") (pin "12") (pinfunction "12_12") (pintype "passive"))
    )
    (net (code "43") (name "Net-(F2-1)") (class "Default")
      (node (ref "F2") (pin "P$1") (pinfunction "1_P$1") (pintype "bidirectional"))
      (node (ref "U$2") (pin "10") (pinfunction "10_10") (pintype "passive"))
      (node (ref "U$2") (pin "9") (pinfunction "9_9") (pintype "passive"))
    )
    (net (code "44") (name "Net-(F3-2)") (class "Default")
      (node (ref "F3") (pin "P$2") (pinfunction "2_P$2") (pintype "bidirectional"))
      (node (ref "U$2") (pin "1") (pinfunction "1_1") (pintype "passive"))
      (node (ref "U$2") (pin "2") (pinfunction "2_2") (pintype "passive"))
    )
    (net (code "45") (name "Net-(IC1A--IN)") (class "Default")
      (node (ref "IC1") (pin "2") (pinfunction "-IN_2") (pintype "input"))
      (node (ref "R300") (pin "1") (pinfunction "1_1") (pintype "passive"))
      (node (ref "R302") (pin "2") (pinfunction "2_2") (pintype "passive"))
    )
    (net (code "46") (name "Net-(IC1A-OUT)") (class "Default")
      (node (ref "IC1") (pin "1") (pinfunction "OUT_1") (pintype "output"))
      (node (ref "R302") (pin "1") (pinfunction "1_1") (pintype "passive"))
      (node (ref "R304") (pin "2") (pinfunction "2_2") (pintype "passive"))
    )
    (net (code "47") (name "Net-(IC1B--IN)") (class "Default")
      (node (ref "IC1") (pin "6") (pinfunction "-IN_6") (pintype "input"))
      (node (ref "R304") (pin "1") (pinfunction "1_1") (pintype "passive"))
      (node (ref "R306") (pin "1") (pinfunction "1_1") (pintype "passive"))
      (node (ref "R308") (pin "2") (pinfunction "2_2") (pintype "passive"))
    )
    (net (code "48") (name "Net-(IC1B-OUT)") (class "Default")
      (node (ref "IC1") (pin "7") (pinfunction "OUT_7") (pintype "output"))
      (node (ref "R308") (pin "1") (pinfunction "1_1") (pintype "passive"))
      (node (ref "R310") (pin "2") (pinfunction "2_2") (pintype "passive"))
    )
    (net (code "49") (name "Net-(IC1C--IN)") (class "Default")
      (node (ref "IC1") (pin "9") (pinfunction "-IN_9") (pintype "input"))
      (node (ref "R301") (pin "1") (pinfunction "1_1") (pintype "passive"))
      (node (ref "R303") (pin "2") (pinfunction "2_2") (pintype "passive"))
    )
    (net (code "50") (name "Net-(IC1C-OUT)") (class "Default")
      (node (ref "IC1") (pin "8") (pinfunction "OUT_8") (pintype "output"))
      (node (ref "R303") (pin "1") (pinfunction "1_1") (pintype "passive"))
      (node (ref "R305") (pin "2") (pinfunction "2_2") (pintype "passive"))
    )
    (net (code "51") (name "Net-(IC1D--IN)") (class "Default")
      (node (ref "IC1") (pin "13") (pinfunction "-IN_13") (pintype "input"))
      (node (ref "R305") (pin "1") (pinfunction "1_1") (pintype "passive"))
      (node (ref "R307") (pin "1") (pinfunction "1_1") (pintype "passive"))
      (node (ref "R309") (pin "2") (pinfunction "2_2") (pintype "passive"))
    )
    (net (code "52") (name "Net-(IC1D-OUT)") (class "Default")
      (node (ref "IC1") (pin "14") (pinfunction "OUT_14") (pintype "output"))
      (node (ref "R309") (pin "1") (pinfunction "1_1") (pintype "passive"))
      (node (ref "R311") (pin "2") (pinfunction "2_2") (pintype "passive"))
    )
    (net (code "53") (name "Net-(IC2A--IN)") (class "Default")
      (node (ref "IC2") (pin "2") (pinfunction "-IN_2") (pintype "input"))
      (node (ref "R500") (pin "2") (pinfunction "2_2") (pintype "passive"))
      (node (ref "R501") (pin "2") (pinfunction "2_2") (pintype "passive"))
      (node (ref "R502") (pin "2") (pinfunction "2_2") (pintype "passive"))
      (node (ref "R503") (pin "1") (pinfunction "1_1") (pintype "passive"))
    )
    (net (code "54") (name "Net-(IC2A-OUT)") (class "Default")
      (node (ref "IC2") (pin "1") (pinfunction "OUT_1") (pintype "output"))
      (node (ref "R503") (pin "2") (pinfunction "2_2") (pintype "passive"))
      (node (ref "R504") (pin "2") (pinfunction "2_2") (pintype "passive"))
    )
    (net (code "55") (name "Net-(IC2B--IN)") (class "Default")
      (node (ref "IC2") (pin "6") (pinfunction "-IN_6") (pintype "input"))
      (node (ref "R600") (pin "2") (pinfunction "2_2") (pintype "passive"))
      (node (ref "R601") (pin "2") (pinfunction "2_2") (pintype "passive"))
      (node (ref "R602") (pin "2") (pinfunction "2_2") (pintype "passive"))
      (node (ref "R603") (pin "1") (pinfunction "1_1") (pintype "passive"))
    )
    (net (code "56") (name "Net-(IC2B-OUT)") (class "Default")
      (node (ref "IC2") (pin "7") (pinfunction "OUT_7") (pintype "output"))
      (node (ref "R603") (pin "2") (pinfunction "2_2") (pintype "passive"))
      (node (ref "R604") (pin "2") (pinfunction "2_2") (pintype "passive"))
    )
    (net (code "57") (name "Net-(IC2C--IN)") (class "Default")
      (node (ref "IC2") (pin "9") (pinfunction "-IN_9") (pintype "input"))
      (node (ref "R700") (pin "2") (pinfunction "2_2") (pintype "passive"))
      (node (ref "R701") (pin "2") (pinfunction "2_2") (pintype "passive"))
      (node (ref "R702") (pin "2") (pinfunction "2_2") (pintype "passive"))
      (node (ref "R703") (pin "1") (pinfunction "1_1") (pintype "passive"))
    )
    (net (code "58") (name "Net-(IC2C-OUT)") (class "Default")
      (node (ref "IC2") (pin "8") (pinfunction "OUT_8") (pintype "output"))
      (node (ref "R703") (pin "2") (pinfunction "2_2") (pintype "passive"))
      (node (ref "R704") (pin "2") (pinfunction "2_2") (pintype "passive"))
    )
    (net (code "59") (name "Net-(IC2D--IN)") (class "Default")
      (node (ref "IC2") (pin "13") (pinfunction "-IN_13") (pintype "input"))
      (node (ref "R800") (pin "2") (pinfunction "2_2") (pintype "passive"))
      (node (ref "R801") (pin "2") (pinfunction "2_2") (pintype "passive"))
      (node (ref "R802") (pin "2") (pinfunction "2_2") (pintype "passive"))
      (node (ref "R803") (pin "1") (pinfunction "1_1") (pintype "passive"))
    )
    (net (code "60") (name "Net-(IC2D-OUT)") (class "Default")
      (node (ref "IC2") (pin "14") (pinfunction "OUT_14") (pintype "output"))
      (node (ref "R803") (pin "2") (pinfunction "2_2") (pintype "passive"))
      (node (ref "R804") (pin "2") (pinfunction "2_2") (pintype "passive"))
    )
    (net (code "61") (name "Net-(IC3A--IN)") (class "Default")
      (node (ref "IC3") (pin "2") (pinfunction "-IN_2") (pintype "input"))
      (node (ref "R400") (pin "2") (pinfunction "2_2") (pintype "passive"))
      (node (ref "R402") (pin "2") (pinfunction "2_2") (pintype "passive"))
      (node (ref "R404") (pin "1") (pinfunction "1_1") (pintype "passive"))
    )
    (net (code "62") (name "Net-(IC3A-OUT)") (class "Default")
      (node (ref "IC3") (pin "1") (pinfunction "OUT_1") (pintype "output"))
      (node (ref "R404") (pin "2") (pinfunction "2_2") (pintype "passive"))
      (node (ref "R406") (pin "1") (pinfunction "1_1") (pintype "passive"))
    )
    (net (code "63") (name "Net-(IC3B--IN)") (class "Default")
      (node (ref "IC3") (pin "6") (pinfunction "-IN_6") (pintype "input"))
      (node (ref "R401") (pin "2") (pinfunction "2_2") (pintype "passive"))
      (node (ref "R403") (pin "2") (pinfunction "2_2") (pintype "passive"))
      (node (ref "R405") (pin "1") (pinfunction "1_1") (pintype "passive"))
    )
    (net (code "64") (name "Net-(IC3B-OUT)") (class "Default")
      (node (ref "IC3") (pin "7") (pinfunction "OUT_7") (pintype "output"))
      (node (ref "R405") (pin "2") (pinfunction "2_2") (pintype "passive"))
      (node (ref "R407") (pin "1") (pinfunction "1_1") (pintype "passive"))
    )
    (net (code "65") (name "Net-(IN_D-3)") (class "Default")
      (node (ref "IN_D") (pin "P$2") (pinfunction "3_P$2") (pintype "passive"))
      (node (ref "R904") (pin "1") (pinfunction "1_1") (pintype "passive"))
    )
    (net (code "66") (name "Net-(OUT_D-3)") (class "Default")
      (node (ref "OUT_D") (pin "P$2") (pinfunction "3_P$2") (pintype "passive"))
      (node (ref "R902") (pin "1") (pinfunction "1_1") (pintype "passive"))
      (node (ref "R903") (pin "2") (pinfunction "2_2") (pintype "passive"))
    )
    (net (code "67") (name "Net-(POT1-Pad2)") (class "Default")
      (node (ref "POT1") (pin "2") (pinfunction "2_2") (pintype "bidirectional"))
      (node (ref "R501") (pin "1") (pinfunction "1_1") (pintype "passive"))
    )
    (net (code "68") (name "Net-(POT2-Pad2)") (class "Default")
      (node (ref "POT2") (pin "2") (pinfunction "2_2") (pintype "bidirectional"))
      (node (ref "R601") (pin "1") (pinfunction "1_1") (pintype "passive"))
    )
    (net (code "69") (name "Net-(POT3-Pad2)") (class "Default")
      (node (ref "POT3") (pin "2") (pinfunction "2_2") (pintype "bidirectional"))
      (node (ref "R701") (pin "1") (pinfunction "1_1") (pintype "passive"))
    )
    (net (code "70") (name "Net-(POT4-Pad2)") (class "Default")
      (node (ref "POT4") (pin "2") (pinfunction "2_2") (pintype "bidirectional"))
      (node (ref "R801") (pin "1") (pinfunction "1_1") (pintype "passive"))
    )
    (net (code "71") (name "Net-(POT5-Pad2)") (class "Default")
      (node (ref "POT5") (pin "2") (pinfunction "2_2") (pintype "bidirectional"))
      (node (ref "R500") (pin "1") (pinfunction "1_1") (pintype "passive"))
    )
    (net (code "72") (name "Net-(POT6-Pad2)") (class "Default")
      (node (ref "POT6") (pin "2") (pinfunction "2_2") (pintype "bidirectional"))
      (node (ref "R600") (pin "1") (pinfunction "1_1") (pintype "passive"))
    )
    (net (code "73") (name "Net-(POT7-Pad2)") (class "Default")
      (node (ref "POT7") (pin "2") (pinfunction "2_2") (pintype "bidirectional"))
      (node (ref "R700") (pin "1") (pinfunction "1_1") (pintype "passive"))
    )
    (net (code "74") (name "Net-(POT8-Pad2)") (class "Default")
      (node (ref "POT8") (pin "2") (pinfunction "2_2") (pintype "bidirectional"))
      (node (ref "R800") (pin "1") (pinfunction "1_1") (pintype "passive"))
    )
    (net (code "75") (name "Net-(Q900-B)") (class "Default")
      (node (ref "Q900") (pin "1") (pinfunction "B_1") (pintype "passive"))
      (node (ref "R900") (pin "2") (pinfunction "2_2") (pintype "passive"))
    )
    (net (code "76") (name "Net-(Q900-C)") (class "Default")
      (node (ref "Q900") (pin "3") (pinfunction "C_3") (pintype "passive"))
      (node (ref "R901") (pin "1") (pinfunction "1_1") (pintype "passive"))
      (node (ref "R902") (pin "2") (pinfunction "2_2") (pintype "passive"))
    )
    (net (code "77") (name "Net-(Q901-B)") (class "Default")
      (node (ref "Q901") (pin "1") (pinfunction "B_1") (pintype "passive"))
      (node (ref "R904") (pin "2") (pinfunction "2_2") (pintype "passive"))
      (node (ref "R905") (pin "2") (pinfunction "2_2") (pintype "passive"))
    )
    (net (code "78") (name "Net-(R101-Pad2)") (class "Default")
      (node (ref "R101") (pin "2") (pinfunction "2_2") (pintype "passive"))
      (node (ref "X1") (pin "D+") (pinfunction "D+_D+") (pintype "bidirectional"))
    )
    (net (code "79") (name "Net-(R102-Pad2)") (class "Default")
      (node (ref "R102") (pin "2") (pinfunction "2_2") (pintype "passive"))
      (node (ref "X1") (pin "D-") (pinfunction "D-_D-") (pintype "bidirectional"))
    )
    (net (code "80") (name "Net-(R103-Pad2)") (class "Default")
      (node (ref "R103") (pin "2") (pinfunction "2_2") (pintype "passive"))
      (node (ref "X1") (pin "VBUS") (pinfunction "VBUS_VBUS") (pintype "bidirectional"))
    )
    (net (code "81") (name "Net-(U$1-LED_R+)") (class "Default")
      (node (ref "R100") (pin "1") (pinfunction "1_1") (pintype "passive"))
      (node (ref "U$1") (pin "+3") (pinfunction "LED_R+_+3") (pintype "input"))
    )
    (net (code "82") (name "VCC{slash}2") (class "Default")
      (node (ref "VMID") (pin "1") (pinfunction "1_1") (pintype "passive"))
    )
    (net (code "83") (name "unconnected-(OUT_D-4-PadP$1)") (class "Default")
      (node (ref "OUT_D") (pin "P$1") (pinfunction "4_P$1") (pintype "passive"))
    )
    (net (code "84") (name "unconnected-(OUT_L-4-PadP$1)") (class "Default")
      (node (ref "OUT_L") (pin "P$1") (pinfunction "4_P$1") (pintype "passive"))
    )
    (net (code "85") (name "unconnected-(OUT_R-4-PadP$1)") (class "Default")
      (node (ref "OUT_R") (pin "P$1") (pinfunction "4_P$1") (pintype "passive"))
    )
    (net (code "86") (name "unconnected-(U$2-Pad13)") (class "Default")
      (node (ref "U$2") (pin "13") (pinfunction "13_13") (pintype "passive"))
    )
    (net (code "87") (name "unconnected-(U$2-Pad14)") (class "Default")
      (node (ref "U$2") (pin "14") (pinfunction "14_14") (pintype "passive"))
    )
    (net (code "88") (name "unconnected-(U$2-Pad15)") (class "Default")
      (node (ref "U$2") (pin "15") (pinfunction "15_15") (pintype "passive"))
    )
    (net (code "89") (name "unconnected-(U$2-Pad16)") (class "Default")
      (node (ref "U$2") (pin "16") (pinfunction "16_16") (pintype "passive"))
    )
  )
)
